# Ethernet.net
KiCad netlist of a schematic drawn in Altium Designer
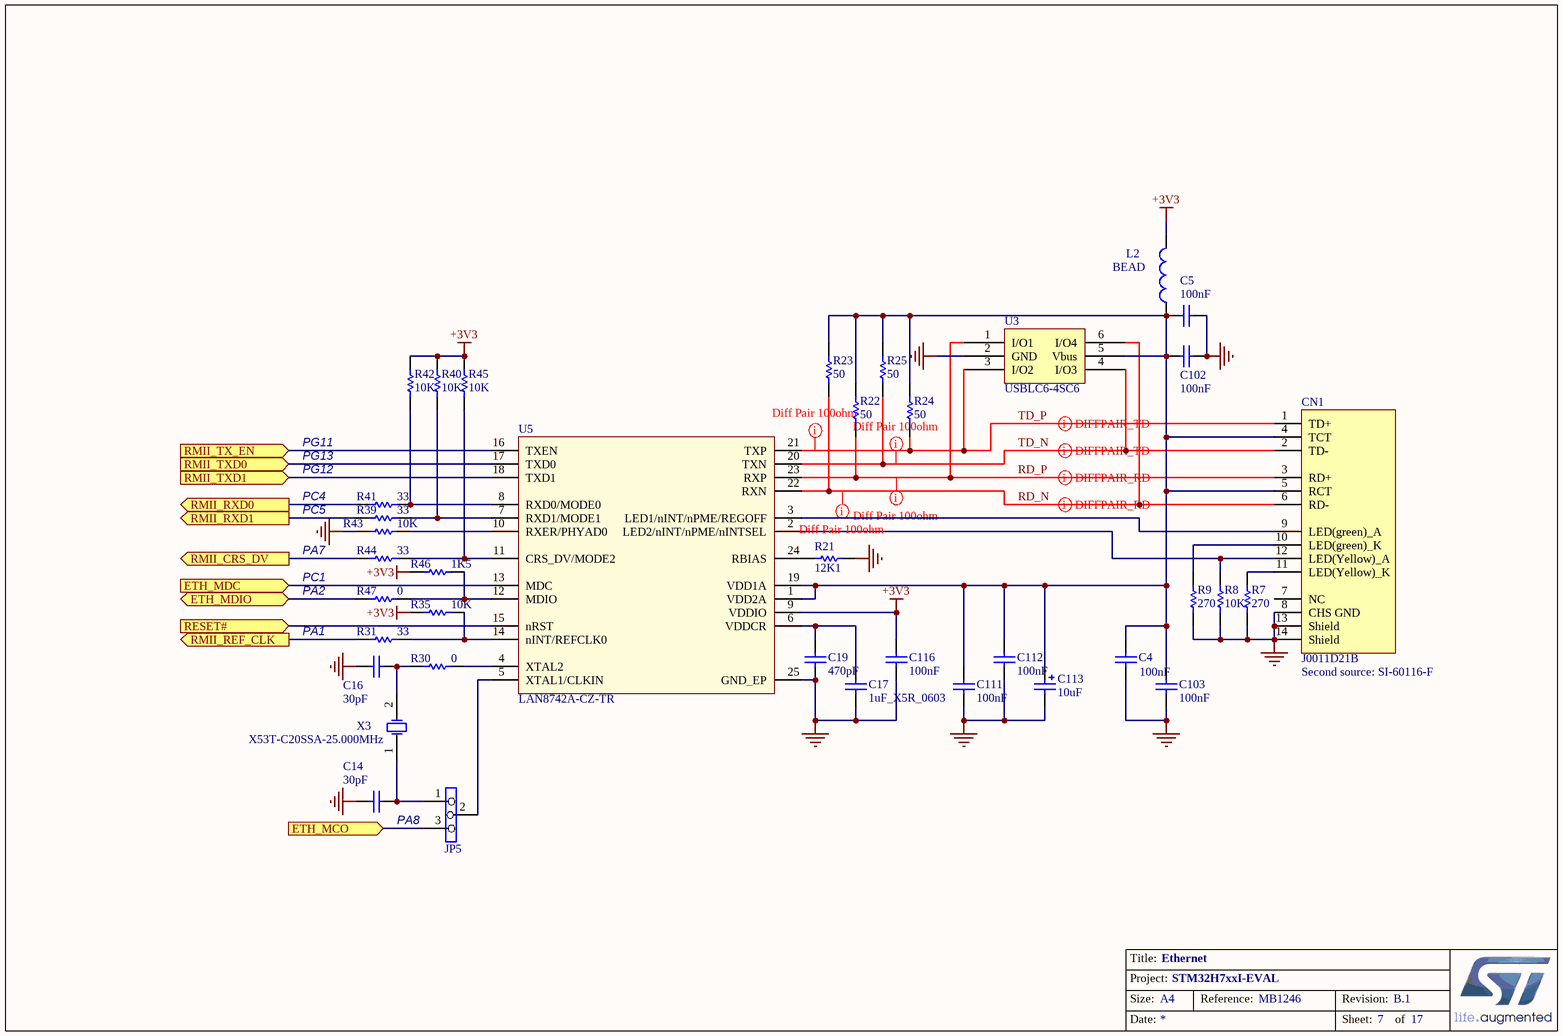
[diagram p0: Ethernet.SchDoc]

(export (version "E")
  (design (tool "Eeschema 10.0.6"))
  (components
    (comp (ref "C4")
      (value "100nF")
      (footprint "0603C")
      (description "Capacitor 0402 / 0603 / 0805")
      (libsource (lib "MCD_TOOLS") (part "Capacitor_ST"))
    )
    (comp (ref "C5")
      (value "100nF")
      (footprint "0603C")
      (description "Capacitor 0402 / 0603 / 0805")
      (libsource (lib "MCD_TOOLS") (part "Capacitor_ST"))
    )
    (comp (ref "C14")
      (value "30pF")
      (footprint "0603C")
      (description "Capacitor 0402 / 0603 / 0805")
      (libsource (lib "MCD_TOOLS") (part "Capacitor_ST"))
    )
    (comp (ref "C16")
      (value "30pF")
      (footprint "0603C")
      (description "Capacitor 0402 / 0603 / 0805")
      (libsource (lib "MCD_TOOLS") (part "Capacitor_ST"))
    )
    (comp (ref "C17")
      (value "1uF_X5R_0603")
      (footprint "0603C")
      (description "0603  X5R 1µF")
      (fields (field (name "TOLERANCE") "10%"))
      (libsource (lib "MB963_1") (part "CAP SMD 0603  X5R 1µF 25V 10%"))
    )
    (comp (ref "C19")
      (value "470pF")
      (footprint "0603C")
      (description "Capacitor 0402 / 0603 / 0805")
      (libsource (lib "MCD_TOOLS") (part "Capacitor_ST"))
    )
    (comp (ref "C102")
      (value "100nF")
      (footprint "0603C")
      (description "Capacitor 0402 / 0603 / 0805")
      (libsource (lib "MCD_TOOLS") (part "Capacitor_ST"))
    )
    (comp (ref "C103")
      (value "100nF")
      (footprint "0603C")
      (description "Capacitor 0402 / 0603 / 0805")
      (libsource (lib "MCD_TOOLS") (part "Capacitor_ST"))
    )
    (comp (ref "C111")
      (value "100nF")
      (footprint "0603C")
      (description "Capacitor 0402 / 0603 / 0805")
      (libsource (lib "MCD_TOOLS") (part "Capacitor_ST"))
    )
    (comp (ref "C112")
      (value "100nF")
      (footprint "0603C")
      (description "Capacitor 0402 / 0603 / 0805")
      (libsource (lib "MCD_TOOLS") (part "Capacitor_ST"))
    )
    (comp (ref "C113")
      (value "10uF")
      (footprint "TAN-A")
      (description "Polarized Capacitor,10uF,10V,10%,typeA,VISHAY")
      (libsource (lib "MCD_TOOLS") (part "Cap_10uF_POL_10%_TANA"))
    )
    (comp (ref "C116")
      (value "100nF")
      (footprint "0603C")
      (description "Capacitor 0402 / 0603 / 0805")
      (libsource (lib "MCD_TOOLS") (part "Capacitor_ST"))
    )
    (comp (ref "CN1")
      (value "J0011D21B")
      (footprint "RJ45_J0011D01BNL")
      (libsource (lib "MB784") (part "J0011D21B"))
    )
    (comp (ref "JP5") (value "~") (footprint "SIP3") (libsource (lib "STR910_SCHLIB") (part "Jumper3")))
    (comp (ref "L2")
      (value "BEAD")
      (footprint "0603L")
      (description "Inductor")
      (fields (field (name "PUBLISHER") "Altium Limited"))
      (libsource (lib "Miscellaneous Devices") (part "Inductor"))
    )
    (comp (ref "R7")
      (value "270")
      (footprint "0603R")
      (description "Resistor 0402 or 0603 or 0805")
      (libsource (lib "Miscellaneous Devices") (part "Res1"))
    )
    (comp (ref "R8")
      (value "10K")
      (footprint "0603R")
      (description "Resistor 0402 or 0603 or 0805")
      (libsource (lib "Miscellaneous Devices") (part "Res1"))
    )
    (comp (ref "R9")
      (value "270")
      (footprint "0603R")
      (description "Resistor 0402 or 0603 or 0805")
      (libsource (lib "Miscellaneous Devices") (part "Res1"))
    )
    (comp (ref "R21")
      (value "12K1")
      (footprint "0603R")
      (description "Resistor,12K1,0603,1%,VISHAY")
      (libsource (lib "MCD_TOOLS") (part "Res_12K1_1%_0603"))
    )
    (comp (ref "R22")
      (value "50")
      (footprint "0603R")
      (description "Resistor,50,0402,1%,YAGEO")
      (libsource (lib "MB1137") (part "Res_50_1%_0603"))
    )
    (comp (ref "R23")
      (value "50")
      (footprint "0603R")
      (description "Resistor,50,0402,1%,YAGEO")
      (libsource (lib "MB1137") (part "Res_50_1%_0603"))
    )
    (comp (ref "R24")
      (value "50")
      (footprint "0603R")
      (description "Resistor,50,0402,1%,YAGEO")
      (libsource (lib "MB1137") (part "Res_50_1%_0603"))
    )
    (comp (ref "R25")
      (value "50")
      (footprint "0603R")
      (description "Resistor,50,0402,1%,YAGEO")
      (libsource (lib "MB1137") (part "Res_50_1%_0603"))
    )
    (comp (ref "R30")
      (value "0")
      (footprint "0603R")
      (description "Resistor")
      (fields (field (name "PUBLISHER") "Altium Limited"))
      (libsource (lib "") (part "Res1_1"))
    )
    (comp (ref "R31")
      (value "33")
      (footprint "0603R")
      (description "Resistor,33,0402,1%,YAGEO")
      (libsource (lib "MCD_TOOLS") (part "Res_33_1%_0402"))
    )
    (comp (ref "R35")
      (value "10K")
      (footprint "0603R")
      (description "Resistor 0402 or 0603 or 0805")
      (libsource (lib "Miscellaneous Devices") (part "Res1"))
    )
    (comp (ref "R39")
      (value "33")
      (footprint "0603R")
      (description "Resistor,33,0402,1%,YAGEO")
      (libsource (lib "MCD_TOOLS") (part "Res_33_1%_0402"))
    )
    (comp (ref "R40")
      (value "10K")
      (footprint "0603R")
      (description "Resistor 0402 or 0603 or 0805")
      (libsource (lib "Miscellaneous Devices") (part "Res1"))
    )
    (comp (ref "R41")
      (value "33")
      (footprint "0603R")
      (description "Resistor,33,0402,1%,YAGEO")
      (libsource (lib "MCD_TOOLS") (part "Res_33_1%_0402"))
    )
    (comp (ref "R42")
      (value "10K")
      (footprint "0603R")
      (description "Resistor 0402 or 0603 or 0805")
      (libsource (lib "Miscellaneous Devices") (part "Res1"))
    )
    (comp (ref "R43")
      (value "10K")
      (footprint "0603R")
      (description "Resistor 0402 or 0603 or 0805")
      (libsource (lib "Miscellaneous Devices") (part "Res1"))
    )
    (comp (ref "R44")
      (value "33")
      (footprint "0603R")
      (description "Resistor,33,0402,1%,YAGEO")
      (libsource (lib "MCD_TOOLS") (part "Res_33_1%_0402"))
    )
    (comp (ref "R45")
      (value "10K")
      (footprint "0603R")
      (description "Resistor 0402 or 0603 or 0805")
      (libsource (lib "Miscellaneous Devices") (part "Res1"))
    )
    (comp (ref "R46")
      (value "1K5")
      (footprint "0603R")
      (description "Resistor,1K5,0402,1%,YAGEO")
      (libsource (lib "MCD_TOOLS") (part "Res_1K5_1%_0402"))
    )
    (comp (ref "R47")
      (value "0")
      (footprint "0603R")
      (description "Resistor")
      (fields (field (name "PUBLISHER") "Altium Limited"))
      (libsource (lib "") (part "Res1_1"))
    )
    (comp (ref "U3")
      (value "USBLC6-4SC6")
      (footprint "SOT23-6")
      (libsource (lib "MB1137_1") (part "USBLC6-4SC6"))
    )
    (comp (ref "U5")
      (value "LAN8742A-CZ-TR")
      (footprint "QFN24_0R5_4X4")
      (libsource (lib "MB1137") (part "LAN8742A-CZ-TR"))
    )
    (comp (ref "X3")
      (value "X53T-C20SSA-25.000MHz")
      (footprint "XTAL_2SM_5X3R2")
      (description "Crystal Oscillator")
      (fields (field (name "PUBLISHER") "Altium Limited"))
      (libsource (lib "MB1137") (part "XTAL_5032"))
    )
  )
  (nets
    (net (code "1") (name "+3V3") (class "Default")
      (node (ref "C116") (pin "2") (pinfunction "2_2") (pintype "passive"))
      (node (ref "L2") (pin "2") (pinfunction "2_2") (pintype "passive"))
      (node (ref "R35") (pin "1") (pinfunction "1_1") (pintype "passive"))
      (node (ref "R40") (pin "1") (pinfunction "1_1") (pintype "passive"))
      (node (ref "R42") (pin "1") (pinfunction "1_1") (pintype "passive"))
      (node (ref "R45") (pin "1") (pinfunction "1_1") (pintype "passive"))
      (node (ref "R46") (pin "2") (pinfunction "2_2") (pintype "passive"))
      (node (ref "U5") (pin "9") (pinfunction "VDDIO_9") (pintype "passive"))
    )
    (net (code "2") (name "/ETH_MCO") (class "Default") (node (ref "JP5") (pin "3") (pintype "passive")))
    (net (code "3") (name "/ETH_MDC") (class "Default")
      (node (ref "U5") (pin "13") (pinfunction "MDC_13") (pintype "passive"))
    )
    (net (code "4") (name "/ETH_MDIO") (class "Default")
      (node (ref "R47") (pin "2") (pinfunction "2_2") (pintype "passive"))
    )
    (net (code "5") (name "/RD_N") (class "Default")
      (node (ref "CN1") (pin "6") (pinfunction "RD-_6") (pintype "passive"))
      (node (ref "R23") (pin "1") (pinfunction "1_1") (pintype "passive"))
      (node (ref "U3") (pin "6") (pinfunction "I/O4_6") (pintype "passive"))
      (node (ref "U5") (pin "22") (pinfunction "RXN_22") (pintype "passive"))
    )
    (net (code "6") (name "/RD_P") (class "Default")
      (node (ref "CN1") (pin "3") (pinfunction "RD+_3") (pintype "passive"))
      (node (ref "R22") (pin "1") (pinfunction "1_1") (pintype "passive"))
      (node (ref "U3") (pin "1") (pinfunction "I/O1_1") (pintype "passive"))
      (node (ref "U5") (pin "23") (pinfunction "RXP_23") (pintype "passive"))
    )
    (net (code "7") (name "/RESET#") (class "Default")
      (node (ref "U5") (pin "15") (pinfunction "nRST_15") (pintype "passive"))
    )
    (net (code "8") (name "/RMII_CRS_DV") (class "Default")
      (node (ref "R44") (pin "2") (pinfunction "2_2") (pintype "passive"))
    )
    (net (code "9") (name "/RMII_REF_CLK") (class "Default")
      (node (ref "R31") (pin "2") (pinfunction "2_2") (pintype "passive"))
    )
    (net (code "10") (name "/RMII_RXD0") (class "Default")
      (node (ref "R41") (pin "2") (pinfunction "2_2") (pintype "passive"))
    )
    (net (code "11") (name "/RMII_RXD1") (class "Default")
      (node (ref "R39") (pin "2") (pinfunction "2_2") (pintype "passive"))
    )
    (net (code "12") (name "/RMII_TXD0") (class "Default")
      (node (ref "U5") (pin "17") (pinfunction "TXD0_17") (pintype "passive"))
    )
    (net (code "13") (name "/RMII_TXD1") (class "Default")
      (node (ref "U5") (pin "18") (pinfunction "TXD1_18") (pintype "passive"))
    )
    (net (code "14") (name "/RMII_TX_EN") (class "Default")
      (node (ref "U5") (pin "16") (pinfunction "TXEN_16") (pintype "passive"))
    )
    (net (code "15") (name "/TD_N") (class "Default")
      (node (ref "CN1") (pin "2") (pinfunction "TD-_2") (pintype "passive"))
      (node (ref "R25") (pin "1") (pinfunction "1_1") (pintype "passive"))
      (node (ref "U3") (pin "4") (pinfunction "I/O3_4") (pintype "passive"))
      (node (ref "U5") (pin "20") (pinfunction "TXN_20") (pintype "passive"))
    )
    (net (code "16") (name "/TD_P") (class "Default")
      (node (ref "CN1") (pin "1") (pinfunction "TD+_1") (pintype "passive"))
      (node (ref "R24") (pin "1") (pinfunction "1_1") (pintype "passive"))
      (node (ref "U3") (pin "3") (pinfunction "I/O2_3") (pintype "passive"))
      (node (ref "U5") (pin "21") (pinfunction "TXP_21") (pintype "passive"))
    )
    (net (code "17") (name "GND") (class "Default")
      (node (ref "C102") (pin "1") (pinfunction "1_1") (pintype "passive"))
      (node (ref "C103") (pin "1") (pinfunction "1_1") (pintype "passive"))
      (node (ref "C111") (pin "1") (pinfunction "1_1") (pintype "passive"))
      (node (ref "C112") (pin "1") (pinfunction "1_1") (pintype "passive"))
      (node (ref "C113") (pin "2") (pinfunction "2_2") (pintype "passive"))
      (node (ref "C116") (pin "1") (pinfunction "1_1") (pintype "passive"))
      (node (ref "C14") (pin "2") (pinfunction "2_2") (pintype "passive"))
      (node (ref "C16") (pin "2") (pinfunction "2_2") (pintype "passive"))
      (node (ref "C17") (pin "2") (pinfunction "2_2") (pintype "passive"))
      (node (ref "C19") (pin "1") (pinfunction "1_1") (pintype "passive"))
      (node (ref "C4") (pin "1") (pinfunction "1_1") (pintype "passive"))
      (node (ref "C5") (pin "1") (pinfunction "1_1") (pintype "passive"))
      (node (ref "CN1") (pin "13") (pinfunction "Shield_13") (pintype "passive"))
      (node (ref "CN1") (pin "14") (pinfunction "Shield_14") (pintype "passive"))
      (node (ref "CN1") (pin "8") (pinfunction "CHS_GND_8") (pintype "passive"))
      (node (ref "R21") (pin "2") (pinfunction "2_2") (pintype "passive"))
      (node (ref "R43") (pin "2") (pinfunction "2_2") (pintype "passive"))
      (node (ref "R7") (pin "2") (pinfunction "2_2") (pintype "passive"))
      (node (ref "R8") (pin "2") (pinfunction "2_2") (pintype "passive"))
      (node (ref "R9") (pin "2") (pinfunction "2_2") (pintype "passive"))
      (node (ref "U3") (pin "2") (pinfunction "GND_2") (pintype "passive"))
      (node (ref "U5") (pin "25") (pinfunction "GND_EP_25") (pintype "passive"))
    )
    (net (code "18") (name "Net-(CN1-LED(Yellow)_A)") (class "Default")
      (node (ref "CN1") (pin "12") (pinfunction "LED(Yellow)_A_12") (pintype "passive"))
      (node (ref "R8") (pin "1") (pinfunction "1_1") (pintype "passive"))
      (node (ref "U5") (pin "2") (pinfunction "LED2/nINT/nPME/nINTSEL_2") (pintype "passive"))
    )
    (net (code "19") (name "Net-(CN1-LED(Yellow)_K)") (class "Default")
      (node (ref "CN1") (pin "11") (pinfunction "LED(Yellow)_K_11") (pintype "passive"))
      (node (ref "R7") (pin "1") (pinfunction "1_1") (pintype "passive"))
    )
    (net (code "20") (name "Net-(CN1-LED(green)_A)") (class "Default")
      (node (ref "CN1") (pin "9") (pinfunction "LED(green)_A_9") (pintype "passive"))
      (node (ref "U5") (pin "3") (pinfunction "LED1/nINT/nPME/REGOFF_3") (pintype "passive"))
    )
    (net (code "21") (name "Net-(CN1-LED(green)_K)") (class "Default")
      (node (ref "CN1") (pin "10") (pinfunction "LED(green)_K_10") (pintype "passive"))
      (node (ref "R9") (pin "1") (pinfunction "1_1") (pintype "passive"))
    )
    (net (code "22") (name "Net-(CN1-RCT)") (class "Default")
      (node (ref "C102") (pin "2") (pinfunction "2_2") (pintype "passive"))
      (node (ref "C103") (pin "2") (pinfunction "2_2") (pintype "passive"))
      (node (ref "C111") (pin "2") (pinfunction "2_2") (pintype "passive"))
      (node (ref "C112") (pin "2") (pinfunction "2_2") (pintype "passive"))
      (node (ref "C113") (pin "1") (pinfunction "1_1") (pintype "passive"))
      (node (ref "C4") (pin "2") (pinfunction "2_2") (pintype "passive"))
      (node (ref "C5") (pin "2") (pinfunction "2_2") (pintype "passive"))
      (node (ref "CN1") (pin "4") (pinfunction "TCT_4") (pintype "passive"))
      (node (ref "CN1") (pin "5") (pinfunction "RCT_5") (pintype "passive"))
      (node (ref "L2") (pin "1") (pinfunction "1_1") (pintype "passive"))
      (node (ref "R22") (pin "2") (pinfunction "2_2") (pintype "passive"))
      (node (ref "R23") (pin "2") (pinfunction "2_2") (pintype "passive"))
      (node (ref "R24") (pin "2") (pinfunction "2_2") (pintype "passive"))
      (node (ref "R25") (pin "2") (pinfunction "2_2") (pintype "passive"))
      (node (ref "U3") (pin "5") (pinfunction "Vbus_5") (pintype "passive"))
      (node (ref "U5") (pin "1") (pinfunction "VDD2A_1") (pintype "passive"))
      (node (ref "U5") (pin "19") (pinfunction "VDD1A_19") (pintype "passive"))
    )
    (net (code "23") (name "Net-(U5-CRS_DV{slash}MODE2)") (class "Default")
      (node (ref "R44") (pin "1") (pinfunction "1_1") (pintype "passive"))
      (node (ref "R45") (pin "2") (pinfunction "2_2") (pintype "passive"))
      (node (ref "U5") (pin "11") (pinfunction "CRS_DV/MODE2_11") (pintype "passive"))
    )
    (net (code "24") (name "Net-(U5-MDIO)") (class "Default")
      (node (ref "R46") (pin "1") (pinfunction "1_1") (pintype "passive"))
      (node (ref "R47") (pin "1") (pinfunction "1_1") (pintype "passive"))
      (node (ref "U5") (pin "12") (pinfunction "MDIO_12") (pintype "passive"))
    )
    (net (code "25") (name "Net-(U5-RBIAS)") (class "Default")
      (node (ref "R21") (pin "1") (pinfunction "1_1") (pintype "passive"))
      (node (ref "U5") (pin "24") (pinfunction "RBIAS_24") (pintype "passive"))
    )
    (net (code "26") (name "Net-(U5-RXD0{slash}MODE0)") (class "Default")
      (node (ref "R41") (pin "1") (pinfunction "1_1") (pintype "passive"))
      (node (ref "R42") (pin "2") (pinfunction "2_2") (pintype "passive"))
      (node (ref "U5") (pin "8") (pinfunction "RXD0/MODE0_8") (pintype "passive"))
    )
    (net (code "27") (name "Net-(U5-RXD1{slash}MODE1)") (class "Default")
      (node (ref "R39") (pin "1") (pinfunction "1_1") (pintype "passive"))
      (node (ref "R40") (pin "2") (pinfunction "2_2") (pintype "passive"))
      (node (ref "U5") (pin "7") (pinfunction "RXD1/MODE1_7") (pintype "passive"))
    )
    (net (code "28") (name "Net-(U5-RXER{slash}PHYAD0)") (class "Default")
      (node (ref "R43") (pin "1") (pinfunction "1_1") (pintype "passive"))
      (node (ref "U5") (pin "10") (pinfunction "RXER/PHYAD0_10") (pintype "passive"))
    )
    (net (code "29") (name "Net-(U5-VDDCR)") (class "Default")
      (node (ref "C17") (pin "1") (pinfunction "1_1") (pintype "passive"))
      (node (ref "C19") (pin "2") (pinfunction "2_2") (pintype "passive"))
      (node (ref "U5") (pin "6") (pinfunction "VDDCR_6") (pintype "passive"))
    )
    (net (code "30") (name "Net-(U5-XTAL1{slash}CLKIN)") (class "Default")
      (node (ref "JP5") (pin "2") (pintype "passive"))
      (node (ref "U5") (pin "5") (pinfunction "XTAL1/CLKIN_5") (pintype "passive"))
    )
    (net (code "31") (name "Net-(U5-XTAL2)") (class "Default")
      (node (ref "R30") (pin "1") (pinfunction "1_1") (pintype "passive"))
      (node (ref "U5") (pin "4") (pinfunction "XTAL2_4") (pintype "passive"))
    )
    (net (code "32") (name "Net-(U5-nINT{slash}REFCLK0)") (class "Default")
      (node (ref "R31") (pin "1") (pinfunction "1_1") (pintype "passive"))
      (node (ref "R35") (pin "2") (pinfunction "2_2") (pintype "passive"))
      (node (ref "U5") (pin "14") (pinfunction "nINT/REFCLK0_14") (pintype "passive"))
    )
    (net (code "33") (name "Net-(X3-OSC1)") (class "Default")
      (node (ref "C14") (pin "1") (pinfunction "1_1") (pintype "passive"))
      (node (ref "JP5") (pin "1") (pintype "passive"))
      (node (ref "X3") (pin "1") (pinfunction "OSC1_1") (pintype "passive"))
    )
    (net (code "34") (name "Net-(X3-OSC2)") (class "Default")
      (node (ref "C16") (pin "1") (pinfunction "1_1") (pintype "passive"))
      (node (ref "R30") (pin "2") (pinfunction "2_2") (pintype "passive"))
      (node (ref "X3") (pin "2") (pinfunction "OSC2_2") (pintype "passive"))
    )
    (net (code "35") (name "unconnected-(CN1-NC-Pad7)") (class "Default")
      (node (ref "CN1") (pin "7") (pinfunction "NC_7") (pintype "passive"))
    )
  )
)
